# arduinoChipophoneShield.net
KiCad netlist of a schematic drawn in EAGLE
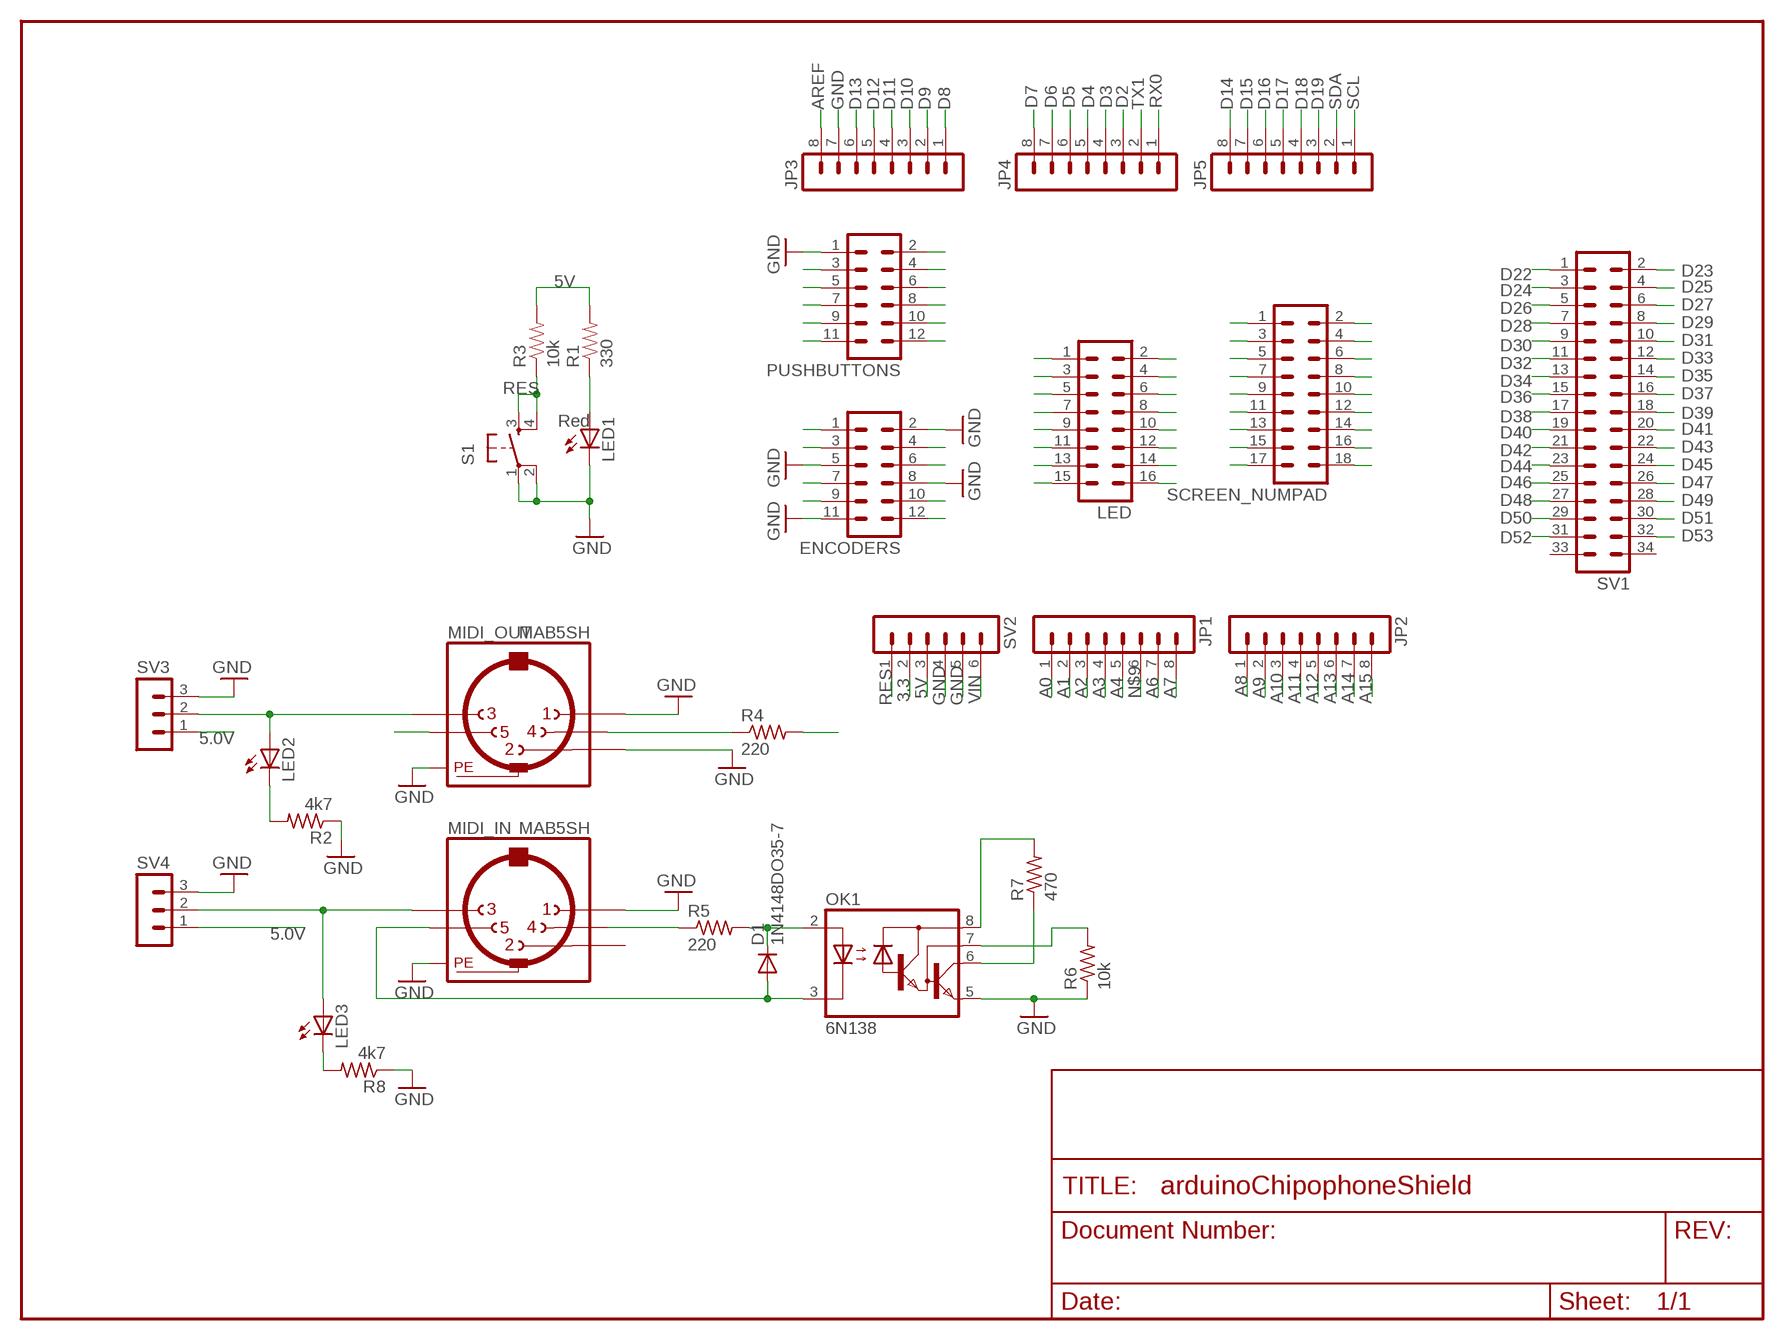
[diagram p0: schematic, sheet 1]

(export (version "E")
  (design (tool "Eeschema 10.0.6"))
  (components
    (comp (ref "D1")
      (value "1N4148DO35-7")
      (footprint "eagle-import:DO35-7")
      (libsource (lib "eagle-import") (part "1N4148DO35-7"))
    )
    (comp (ref "ENCODERS")
      (value "MA06-2")
      (footprint "eagle-import:MA06-2")
      (libsource (lib "eagle-import") (part "MA06-2"))
    )
    (comp (ref "JP1")
      (value "MA08-1")
      (footprint "eagle-import:MA08-1")
      (libsource (lib "eagle-import") (part "MA08-1"))
    )
    (comp (ref "JP2")
      (value "MA08-1")
      (footprint "eagle-import:MA08-1")
      (libsource (lib "eagle-import") (part "MA08-1"))
    )
    (comp (ref "JP3")
      (value "MA08-1")
      (footprint "eagle-import:MA08-1")
      (libsource (lib "eagle-import") (part "MA08-1"))
    )
    (comp (ref "JP4")
      (value "MA08-1")
      (footprint "eagle-import:MA08-1")
      (libsource (lib "eagle-import") (part "MA08-1"))
    )
    (comp (ref "JP5")
      (value "MA08-1")
      (footprint "eagle-import:MA08-1")
      (libsource (lib "eagle-import") (part "MA08-1"))
    )
    (comp (ref "LED")
      (value "MA08-2")
      (footprint "eagle-import:MA08-2")
      (libsource (lib "eagle-import") (part "MA08-2"))
    )
    (comp (ref "LED1")
      (value "Red")
      (footprint "eagle-import:LED5MM")
      (libsource (lib "eagle-import") (part "LED5MM"))
    )
    (comp (ref "LED2")
      (value "LEDLSU260")
      (footprint "eagle-import:LSU260")
      (libsource (lib "eagle-import") (part "LEDLSU260"))
    )
    (comp (ref "LED3")
      (value "LEDLSU260")
      (footprint "eagle-import:LSU260")
      (libsource (lib "eagle-import") (part "LEDLSU260"))
    )
    (comp (ref "MIDI_IN")
      (value "MAB5SH")
      (footprint "eagle-import:MAB5SH")
      (libsource (lib "eagle-import") (part "MAB5SH"))
    )
    (comp (ref "MIDI_OUT")
      (value "MAB5SH")
      (footprint "eagle-import:MAB5SH")
      (libsource (lib "eagle-import") (part "MAB5SH"))
    )
    (comp (ref "OK1")
      (value "6N138")
      (footprint "eagle-import:DIL08")
      (fields (field (name "MF") "VISHAY/TELEFUNKEN"))
      (libsource (lib "eagle-import") (part "6N138"))
    )
    (comp (ref "PUSHBUTTONS")
      (value "MA06-2")
      (footprint "eagle-import:MA06-2")
      (libsource (lib "eagle-import") (part "MA06-2"))
    )
    (comp (ref "R1")
      (value "330")
      (footprint "eagle-import:AXIAL-0.3")
      (libsource (lib "eagle-import") (part "RESISTORPTH1"))
    )
    (comp (ref "R2")
      (value "4k7")
      (footprint "eagle-import:0204_7")
      (libsource (lib "eagle-import") (part "resistor_R-US_0204/7"))
    )
    (comp (ref "R3")
      (value "10k")
      (footprint "eagle-import:AXIAL-0.3")
      (libsource (lib "eagle-import") (part "RESISTORPTH1"))
    )
    (comp (ref "R4")
      (value "220")
      (footprint "eagle-import:0204_7")
      (libsource (lib "eagle-import") (part "R-US_0204/7"))
    )
    (comp (ref "R5")
      (value "220")
      (footprint "eagle-import:0204_7")
      (libsource (lib "eagle-import") (part "R-US_0204/7"))
    )
    (comp (ref "R6")
      (value "10k")
      (footprint "eagle-import:0204_7")
      (libsource (lib "eagle-import") (part "R-US_0204/7"))
    )
    (comp (ref "R7")
      (value "470")
      (footprint "eagle-import:0204_7")
      (libsource (lib "eagle-import") (part "R-US_0204/7"))
    )
    (comp (ref "R8")
      (value "4k7")
      (footprint "eagle-import:0204_7")
      (libsource (lib "eagle-import") (part "resistor_R-US_0204/7"))
    )
    (comp (ref "S1")
      (value "TAC_SWITCHPTH")
      (footprint "eagle-import:TACTILE-PTH")
      (libsource (lib "eagle-import") (part "TAC_SWITCHPTH"))
    )
    (comp (ref "SCREEN_NUMPAD")
      (value "MA09-2")
      (footprint "eagle-import:MA09-2")
      (libsource (lib "eagle-import") (part "MA09-2"))
    )
    (comp (ref "SV1")
      (value "MA17-2")
      (footprint "eagle-import:MA17-2")
      (libsource (lib "eagle-import") (part "MA17-2"))
    )
    (comp (ref "SV2")
      (value "MA06-1")
      (footprint "eagle-import:MA06-1")
      (libsource (lib "eagle-import") (part "MA06-1"))
    )
    (comp (ref "SV3")
      (value "MA03-1")
      (footprint "eagle-import:MA03-1")
      (libsource (lib "eagle-import") (part "MA03-1"))
    )
    (comp (ref "SV4")
      (value "MA03-1")
      (footprint "eagle-import:MA03-1")
      (libsource (lib "eagle-import") (part "MA03-1"))
    )
  )
  (nets
    (net (code "1") (name "/3.3") (class "Default")
      (node (ref "SV2") (pin "2") (pinfunction "2_2") (pintype "passive"))
    )
    (net (code "2") (name "/5.0V") (class "Default")
      (node (ref "LED") (pin "1") (pinfunction "1_1") (pintype "passive"))
      (node (ref "OK1") (pin "8") (pinfunction "VCC_8") (pintype "passive"))
      (node (ref "R1") (pin "P$2") (pinfunction "2_P$2") (pintype "passive"))
      (node (ref "R3") (pin "P$2") (pinfunction "2_P$2") (pintype "passive"))
      (node (ref "R4") (pin "2") (pinfunction "2_2") (pintype "passive"))
      (node (ref "R7") (pin "2") (pinfunction "2_2") (pintype "passive"))
      (node (ref "SCREEN_NUMPAD") (pin "1") (pinfunction "1_1") (pintype "passive"))
      (node (ref "SCREEN_NUMPAD") (pin "9") (pinfunction "9_9") (pintype "passive"))
      (node (ref "SV2") (pin "3") (pinfunction "3_3") (pintype "passive"))
      (node (ref "SV3") (pin "1") (pinfunction "1_1") (pintype "passive"))
      (node (ref "SV4") (pin "1") (pinfunction "1_1") (pintype "passive"))
    )
    (net (code "3") (name "/A0") (class "Default")
      (node (ref "JP1") (pin "1") (pinfunction "1_1") (pintype "passive"))
      (node (ref "SCREEN_NUMPAD") (pin "11") (pinfunction "11_11") (pintype "passive"))
    )
    (net (code "4") (name "/A1") (class "Default")
      (node (ref "JP1") (pin "2") (pinfunction "2_2") (pintype "passive"))
      (node (ref "SCREEN_NUMPAD") (pin "12") (pinfunction "12_12") (pintype "passive"))
    )
    (net (code "5") (name "/A2") (class "Default")
      (node (ref "JP1") (pin "3") (pinfunction "3_3") (pintype "passive"))
      (node (ref "SCREEN_NUMPAD") (pin "13") (pinfunction "13_13") (pintype "passive"))
    )
    (net (code "6") (name "/A3") (class "Default")
      (node (ref "JP1") (pin "4") (pinfunction "4_4") (pintype "passive"))
      (node (ref "SCREEN_NUMPAD") (pin "14") (pinfunction "14_14") (pintype "passive"))
    )
    (net (code "7") (name "/A4") (class "Default")
      (node (ref "JP1") (pin "5") (pinfunction "5_5") (pintype "passive"))
      (node (ref "SCREEN_NUMPAD") (pin "15") (pinfunction "15_15") (pintype "passive"))
    )
    (net (code "8") (name "/A6") (class "Default")
      (node (ref "JP1") (pin "7") (pinfunction "7_7") (pintype "passive"))
      (node (ref "SCREEN_NUMPAD") (pin "17") (pinfunction "17_17") (pintype "passive"))
    )
    (net (code "9") (name "/A7") (class "Default")
      (node (ref "JP1") (pin "8") (pinfunction "8_8") (pintype "passive"))
      (node (ref "SCREEN_NUMPAD") (pin "18") (pinfunction "18_18") (pintype "passive"))
    )
    (net (code "10") (name "/A8") (class "Default")
      (node (ref "JP2") (pin "1") (pinfunction "1_1") (pintype "passive"))
    )
    (net (code "11") (name "/A9") (class "Default")
      (node (ref "JP2") (pin "2") (pinfunction "2_2") (pintype "passive"))
    )
    (net (code "12") (name "/A10") (class "Default")
      (node (ref "JP2") (pin "3") (pinfunction "3_3") (pintype "passive"))
    )
    (net (code "13") (name "/A11") (class "Default")
      (node (ref "JP2") (pin "4") (pinfunction "4_4") (pintype "passive"))
    )
    (net (code "14") (name "/A12") (class "Default")
      (node (ref "JP2") (pin "5") (pinfunction "5_5") (pintype "passive"))
    )
    (net (code "15") (name "/A13") (class "Default")
      (node (ref "JP2") (pin "6") (pinfunction "6_6") (pintype "passive"))
    )
    (net (code "16") (name "/A14") (class "Default")
      (node (ref "JP2") (pin "7") (pinfunction "7_7") (pintype "passive"))
    )
    (net (code "17") (name "/A15") (class "Default")
      (node (ref "JP2") (pin "8") (pinfunction "8_8") (pintype "passive"))
    )
    (net (code "18") (name "/AREF") (class "Default")
      (node (ref "JP3") (pin "8") (pinfunction "8_8") (pintype "passive"))
    )
    (net (code "19") (name "/D2") (class "Default")
      (node (ref "JP4") (pin "3") (pinfunction "3_3") (pintype "passive"))
      (node (ref "LED") (pin "2") (pinfunction "2_2") (pintype "passive"))
    )
    (net (code "20") (name "/D3") (class "Default")
      (node (ref "JP4") (pin "4") (pinfunction "4_4") (pintype "passive"))
      (node (ref "LED") (pin "3") (pinfunction "3_3") (pintype "passive"))
    )
    (net (code "21") (name "/D4") (class "Default")
      (node (ref "JP4") (pin "5") (pinfunction "5_5") (pintype "passive"))
      (node (ref "LED") (pin "4") (pinfunction "4_4") (pintype "passive"))
    )
    (net (code "22") (name "/D5") (class "Default")
      (node (ref "JP4") (pin "6") (pinfunction "6_6") (pintype "passive"))
      (node (ref "LED") (pin "5") (pinfunction "5_5") (pintype "passive"))
    )
    (net (code "23") (name "/D6") (class "Default")
      (node (ref "JP4") (pin "7") (pinfunction "7_7") (pintype "passive"))
      (node (ref "LED") (pin "6") (pinfunction "6_6") (pintype "passive"))
    )
    (net (code "24") (name "/D7") (class "Default")
      (node (ref "JP4") (pin "8") (pinfunction "8_8") (pintype "passive"))
      (node (ref "LED") (pin "7") (pinfunction "7_7") (pintype "passive"))
    )
    (net (code "25") (name "/D8") (class "Default")
      (node (ref "JP3") (pin "1") (pinfunction "1_1") (pintype "passive"))
      (node (ref "LED") (pin "8") (pinfunction "8_8") (pintype "passive"))
    )
    (net (code "26") (name "/D9") (class "Default")
      (node (ref "JP3") (pin "2") (pinfunction "2_2") (pintype "passive"))
      (node (ref "LED") (pin "9") (pinfunction "9_9") (pintype "passive"))
    )
    (net (code "27") (name "/D10") (class "Default")
      (node (ref "JP3") (pin "3") (pinfunction "3_3") (pintype "passive"))
      (node (ref "LED") (pin "10") (pinfunction "10_10") (pintype "passive"))
    )
    (net (code "28") (name "/D11") (class "Default")
      (node (ref "JP3") (pin "4") (pinfunction "4_4") (pintype "passive"))
      (node (ref "LED") (pin "11") (pinfunction "11_11") (pintype "passive"))
    )
    (net (code "29") (name "/D12") (class "Default")
      (node (ref "JP3") (pin "5") (pinfunction "5_5") (pintype "passive"))
      (node (ref "LED") (pin "12") (pinfunction "12_12") (pintype "passive"))
    )
    (net (code "30") (name "/D13") (class "Default")
      (node (ref "JP3") (pin "6") (pinfunction "6_6") (pintype "passive"))
      (node (ref "LED") (pin "13") (pinfunction "13_13") (pintype "passive"))
    )
    (net (code "31") (name "/D14") (class "Default")
      (node (ref "JP5") (pin "8") (pinfunction "8_8") (pintype "passive"))
    )
    (net (code "32") (name "/D15") (class "Default")
      (node (ref "JP5") (pin "7") (pinfunction "7_7") (pintype "passive"))
    )
    (net (code "33") (name "/D16") (class "Default")
      (node (ref "JP5") (pin "6") (pinfunction "6_6") (pintype "passive"))
    )
    (net (code "34") (name "/D17") (class "Default")
      (node (ref "JP5") (pin "5") (pinfunction "5_5") (pintype "passive"))
    )
    (net (code "35") (name "/D18") (class "Default")
      (node (ref "JP5") (pin "4") (pinfunction "4_4") (pintype "passive"))
      (node (ref "MIDI_OUT") (pin "5") (pinfunction "5_5") (pintype "passive"))
    )
    (net (code "36") (name "/D19") (class "Default")
      (node (ref "JP5") (pin "3") (pinfunction "3_3") (pintype "passive"))
      (node (ref "OK1") (pin "6") (pinfunction "VO_6") (pintype "passive"))
      (node (ref "R7") (pin "1") (pinfunction "1_1") (pintype "passive"))
    )
    (net (code "37") (name "/D22") (class "Default")
      (node (ref "PUSHBUTTONS") (pin "2") (pinfunction "2_2") (pintype "passive"))
      (node (ref "SV1") (pin "1") (pinfunction "1_1") (pintype "passive"))
    )
    (net (code "38") (name "/D23") (class "Default")
      (node (ref "PUSHBUTTONS") (pin "3") (pinfunction "3_3") (pintype "passive"))
      (node (ref "SV1") (pin "2") (pinfunction "2_2") (pintype "passive"))
    )
    (net (code "39") (name "/D24") (class "Default")
      (node (ref "PUSHBUTTONS") (pin "4") (pinfunction "4_4") (pintype "passive"))
      (node (ref "SV1") (pin "3") (pinfunction "3_3") (pintype "passive"))
    )
    (net (code "40") (name "/D25") (class "Default")
      (node (ref "PUSHBUTTONS") (pin "5") (pinfunction "5_5") (pintype "passive"))
      (node (ref "SV1") (pin "4") (pinfunction "4_4") (pintype "passive"))
    )
    (net (code "41") (name "/D26") (class "Default")
      (node (ref "PUSHBUTTONS") (pin "6") (pinfunction "6_6") (pintype "passive"))
      (node (ref "SV1") (pin "5") (pinfunction "5_5") (pintype "passive"))
    )
    (net (code "42") (name "/D27") (class "Default")
      (node (ref "PUSHBUTTONS") (pin "7") (pinfunction "7_7") (pintype "passive"))
      (node (ref "SV1") (pin "6") (pinfunction "6_6") (pintype "passive"))
    )
    (net (code "43") (name "/D28") (class "Default")
      (node (ref "PUSHBUTTONS") (pin "8") (pinfunction "8_8") (pintype "passive"))
      (node (ref "SV1") (pin "7") (pinfunction "7_7") (pintype "passive"))
    )
    (net (code "44") (name "/D29") (class "Default")
      (node (ref "PUSHBUTTONS") (pin "9") (pinfunction "9_9") (pintype "passive"))
      (node (ref "SV1") (pin "8") (pinfunction "8_8") (pintype "passive"))
    )
    (net (code "45") (name "/D30") (class "Default")
      (node (ref "PUSHBUTTONS") (pin "10") (pinfunction "10_10") (pintype "passive"))
      (node (ref "SV1") (pin "9") (pinfunction "9_9") (pintype "passive"))
    )
    (net (code "46") (name "/D31") (class "Default")
      (node (ref "PUSHBUTTONS") (pin "11") (pinfunction "11_11") (pintype "passive"))
      (node (ref "SV1") (pin "10") (pinfunction "10_10") (pintype "passive"))
    )
    (net (code "47") (name "/D32") (class "Default")
      (node (ref "PUSHBUTTONS") (pin "12") (pinfunction "12_12") (pintype "passive"))
      (node (ref "SV1") (pin "11") (pinfunction "11_11") (pintype "passive"))
    )
    (net (code "48") (name "/D33") (class "Default")
      (node (ref "ENCODERS") (pin "1") (pinfunction "1_1") (pintype "passive"))
      (node (ref "SV1") (pin "12") (pinfunction "12_12") (pintype "passive"))
    )
    (net (code "49") (name "/D34") (class "Default")
      (node (ref "ENCODERS") (pin "3") (pinfunction "3_3") (pintype "passive"))
      (node (ref "SV1") (pin "13") (pinfunction "13_13") (pintype "passive"))
    )
    (net (code "50") (name "/D35") (class "Default")
      (node (ref "ENCODERS") (pin "4") (pinfunction "4_4") (pintype "passive"))
      (node (ref "SV1") (pin "14") (pinfunction "14_14") (pintype "passive"))
    )
    (net (code "51") (name "/D36") (class "Default")
      (node (ref "ENCODERS") (pin "6") (pinfunction "6_6") (pintype "passive"))
      (node (ref "SV1") (pin "15") (pinfunction "15_15") (pintype "passive"))
    )
    (net (code "52") (name "/D37") (class "Default")
      (node (ref "ENCODERS") (pin "7") (pinfunction "7_7") (pintype "passive"))
      (node (ref "SV1") (pin "16") (pinfunction "16_16") (pintype "passive"))
    )
    (net (code "53") (name "/D38") (class "Default")
      (node (ref "ENCODERS") (pin "9") (pinfunction "9_9") (pintype "passive"))
      (node (ref "SV1") (pin "17") (pinfunction "17_17") (pintype "passive"))
    )
    (net (code "54") (name "/D39") (class "Default")
      (node (ref "ENCODERS") (pin "10") (pinfunction "10_10") (pintype "passive"))
      (node (ref "SV1") (pin "18") (pinfunction "18_18") (pintype "passive"))
    )
    (net (code "55") (name "/D40") (class "Default")
      (node (ref "ENCODERS") (pin "12") (pinfunction "12_12") (pintype "passive"))
      (node (ref "SV1") (pin "19") (pinfunction "19_19") (pintype "passive"))
    )
    (net (code "56") (name "/D41") (class "Default")
      (node (ref "SV1") (pin "20") (pinfunction "20_20") (pintype "passive"))
    )
    (net (code "57") (name "/D42") (class "Default")
      (node (ref "SV1") (pin "21") (pinfunction "21_21") (pintype "passive"))
    )
    (net (code "58") (name "/D43") (class "Default")
      (node (ref "SV1") (pin "22") (pinfunction "22_22") (pintype "passive"))
    )
    (net (code "59") (name "/D44") (class "Default")
      (node (ref "LED") (pin "14") (pinfunction "14_14") (pintype "passive"))
      (node (ref "SV1") (pin "23") (pinfunction "23_23") (pintype "passive"))
    )
    (net (code "60") (name "/D45") (class "Default")
      (node (ref "LED") (pin "15") (pinfunction "15_15") (pintype "passive"))
      (node (ref "SV1") (pin "24") (pinfunction "24_24") (pintype "passive"))
    )
    (net (code "61") (name "/D46") (class "Default")
      (node (ref "LED") (pin "16") (pinfunction "16_16") (pintype "passive"))
      (node (ref "SV1") (pin "25") (pinfunction "25_25") (pintype "passive"))
    )
    (net (code "62") (name "/D47") (class "Default")
      (node (ref "SV1") (pin "26") (pinfunction "26_26") (pintype "passive"))
    )
    (net (code "63") (name "/D48") (class "Default")
      (node (ref "SCREEN_NUMPAD") (pin "6") (pinfunction "6_6") (pintype "passive"))
      (node (ref "SV1") (pin "27") (pinfunction "27_27") (pintype "passive"))
    )
    (net (code "64") (name "/D49") (class "Default")
      (node (ref "SCREEN_NUMPAD") (pin "7") (pinfunction "7_7") (pintype "passive"))
      (node (ref "SV1") (pin "28") (pinfunction "28_28") (pintype "passive"))
    )
    (net (code "65") (name "/D50") (class "Default")
      (node (ref "SCREEN_NUMPAD") (pin "2") (pinfunction "2_2") (pintype "passive"))
      (node (ref "SV1") (pin "29") (pinfunction "29_29") (pintype "passive"))
    )
    (net (code "66") (name "/D51") (class "Default")
      (node (ref "SCREEN_NUMPAD") (pin "4") (pinfunction "4_4") (pintype "passive"))
      (node (ref "SV1") (pin "30") (pinfunction "30_30") (pintype "passive"))
    )
    (net (code "67") (name "/D52") (class "Default")
      (node (ref "SCREEN_NUMPAD") (pin "3") (pinfunction "3_3") (pintype "passive"))
      (node (ref "SV1") (pin "31") (pinfunction "31_31") (pintype "passive"))
    )
    (net (code "68") (name "/D53") (class "Default")
      (node (ref "SCREEN_NUMPAD") (pin "5") (pinfunction "5_5") (pintype "passive"))
      (node (ref "SV1") (pin "32") (pinfunction "32_32") (pintype "passive"))
    )
    (net (code "69") (name "/N$9") (class "Default")
      (node (ref "JP1") (pin "6") (pinfunction "6_6") (pintype "passive"))
      (node (ref "SCREEN_NUMPAD") (pin "16") (pinfunction "16_16") (pintype "passive"))
    )
    (net (code "70") (name "/RES") (class "Default")
      (node (ref "R3") (pin "P$1") (pinfunction "1_P$1") (pintype "passive"))
      (node (ref "S1") (pin "3") (pinfunction "3_3") (pintype "passive"))
      (node (ref "S1") (pin "4") (pinfunction "4_4") (pintype "passive"))
      (node (ref "SCREEN_NUMPAD") (pin "8") (pinfunction "8_8") (pintype "passive"))
      (node (ref "SV2") (pin "1") (pinfunction "1_1") (pintype "passive"))
    )
    (net (code "71") (name "/RX0") (class "Default")
      (node (ref "JP4") (pin "1") (pinfunction "1_1") (pintype "passive"))
    )
    (net (code "72") (name "/SCL") (class "Default")
      (node (ref "JP5") (pin "1") (pinfunction "1_1") (pintype "passive"))
    )
    (net (code "73") (name "/SDA") (class "Default")
      (node (ref "JP5") (pin "2") (pinfunction "2_2") (pintype "passive"))
    )
    (net (code "74") (name "/TX1") (class "Default")
      (node (ref "JP4") (pin "2") (pinfunction "2_2") (pintype "passive"))
    )
    (net (code "75") (name "/VIN") (class "Default")
      (node (ref "SV2") (pin "6") (pinfunction "6_6") (pintype "passive"))
    )
    (net (code "76") (name "GND") (class "Default")
      (node (ref "ENCODERS") (pin "11") (pinfunction "11_11") (pintype "passive"))
      (node (ref "ENCODERS") (pin "2") (pinfunction "2_2") (pintype "passive"))
      (node (ref "ENCODERS") (pin "5") (pinfunction "5_5") (pintype "passive"))
      (node (ref "ENCODERS") (pin "8") (pinfunction "8_8") (pintype "passive"))
      (node (ref "JP3") (pin "7") (pinfunction "7_7") (pintype "passive"))
      (node (ref "LED1") (pin "K") (pinfunction "C_K") (pintype "passive"))
      (node (ref "MIDI_IN") (pin "1") (pinfunction "1_1") (pintype "passive"))
      (node (ref "MIDI_IN") (pin "PE") (pinfunction "PE_PE") (pintype "power_in"))
      (node (ref "MIDI_IN") (pin "PE@") (pinfunction "PE_PE@") (pintype "power_in"))
      (node (ref "MIDI_OUT") (pin "1") (pinfunction "1_1") (pintype "passive"))
      (node (ref "MIDI_OUT") (pin "2") (pinfunction "2_2") (pintype "passive"))
      (node (ref "MIDI_OUT") (pin "PE") (pinfunction "PE_PE") (pintype "power_in"))
      (node (ref "MIDI_OUT") (pin "PE@") (pinfunction "PE_PE@") (pintype "power_in"))
      (node (ref "OK1") (pin "5") (pinfunction "GND_5") (pintype "passive"))
      (node (ref "PUSHBUTTONS") (pin "1") (pinfunction "1_1") (pintype "passive"))
      (node (ref "R2") (pin "1") (pinfunction "1_1") (pintype "passive"))
      (node (ref "R6") (pin "1") (pinfunction "1_1") (pintype "passive"))
      (node (ref "R8") (pin "1") (pinfunction "1_1") (pintype "passive"))
      (node (ref "S1") (pin "1") (pinfunction "1_1") (pintype "passive"))
      (node (ref "S1") (pin "2") (pinfunction "2_2") (pintype "passive"))
      (node (ref "SCREEN_NUMPAD") (pin "10") (pinfunction "10_10") (pintype "passive"))
      (node (ref "SV2") (pin "4") (pinfunction "4_4") (pintype "passive"))
      (node (ref "SV2") (pin "5") (pinfunction "5_5") (pintype "passive"))
      (node (ref "SV3") (pin "3") (pinfunction "3_3") (pintype "passive"))
      (node (ref "SV4") (pin "3") (pinfunction "3_3") (pintype "passive"))
    )
    (net (code "77") (name "Net-(LED2-C)") (class "Default")
      (node (ref "LED2") (pin "K") (pinfunction "C_K") (pintype "passive"))
      (node (ref "R2") (pin "2") (pinfunction "2_2") (pintype "passive"))
    )
    (net (code "78") (name "Net-(LED2-PadA)") (class "Default")
      (node (ref "LED2") (pin "A") (pinfunction "A_A") (pintype "passive"))
      (node (ref "MIDI_OUT") (pin "3") (pinfunction "3_3") (pintype "passive"))
      (node (ref "SV3") (pin "2") (pinfunction "2_2") (pintype "passive"))
    )
    (net (code "79") (name "Net-(LED3-C)") (class "Default")
      (node (ref "LED3") (pin "K") (pinfunction "C_K") (pintype "passive"))
      (node (ref "R8") (pin "2") (pinfunction "2_2") (pintype "passive"))
    )
    (net (code "80") (name "Net-(LED3-PadA)") (class "Default")
      (node (ref "LED3") (pin "A") (pinfunction "A_A") (pintype "passive"))
      (node (ref "MIDI_IN") (pin "3") (pinfunction "3_3") (pintype "passive"))
      (node (ref "SV4") (pin "2") (pinfunction "2_2") (pintype "passive"))
    )
    (net (code "81") (name "Net-(MIDI_IN-Pad4)") (class "Default")
      (node (ref "MIDI_IN") (pin "4") (pinfunction "4_4") (pintype "passive"))
      (node (ref "R5") (pin "1") (pinfunction "1_1") (pintype "passive"))
    )
    (net (code "82") (name "Net-(MIDI_OUT-Pad4)") (class "Default")
      (node (ref "MIDI_OUT") (pin "4") (pinfunction "4_4") (pintype "passive"))
      (node (ref "R4") (pin "1") (pinfunction "1_1") (pintype "passive"))
    )
    (net (code "83") (name "Net-(OK1-A)") (class "Default")
      (node (ref "D1") (pin "C") (pinfunction "C_C") (pintype "passive"))
      (node (ref "OK1") (pin "2") (pinfunction "A_2") (pintype "passive"))
      (node (ref "R5") (pin "2") (pinfunction "2_2") (pintype "passive"))
    )
    (net (code "84") (name "Net-(OK1-C)") (class "Default")
      (node (ref "D1") (pin "A") (pinfunction "A_A") (pintype "passive"))
      (node (ref "MIDI_IN") (pin "5") (pinfunction "5_5") (pintype "passive"))
      (node (ref "OK1") (pin "3") (pinfunction "C_3") (pintype "passive"))
    )
    (net (code "85") (name "Net-(OK1-VB)") (class "Default")
      (node (ref "OK1") (pin "7") (pinfunction "VB_7") (pintype "passive"))
      (node (ref "R6") (pin "2") (pinfunction "2_2") (pintype "passive"))
    )
    (net (code "86") (name "Net-(R1-1)") (class "Default")
      (node (ref "LED1") (pin "A") (pinfunction "A_A") (pintype "passive"))
      (node (ref "R1") (pin "P$1") (pinfunction "1_P$1") (pintype "passive"))
    )
    (net (code "87") (name "unconnected-(MIDI_IN-Pad2)") (class "Default")
      (node (ref "MIDI_IN") (pin "2") (pinfunction "2_2") (pintype "passive"))
    )
    (net (code "88") (name "unconnected-(SV1-Pad33)") (class "Default")
      (node (ref "SV1") (pin "33") (pinfunction "33_33") (pintype "passive"))
    )
    (net (code "89") (name "unconnected-(SV1-Pad34)") (class "Default")
      (node (ref "SV1") (pin "34") (pinfunction "34_34") (pintype "passive"))
    )
  )
)
